# DCM_module_board.net
KiCad netlist of a schematic drawn in EAGLE
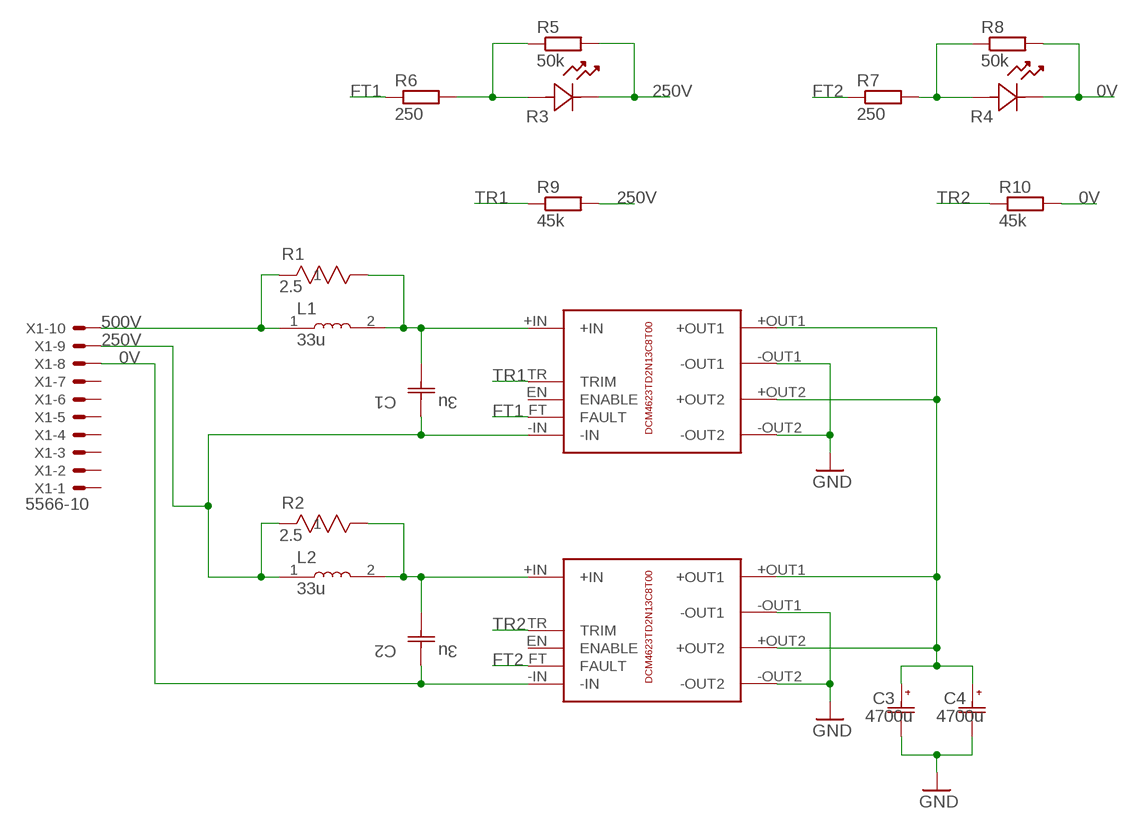
[diagram p0: schematic, sheet 1]

(export (version "E")
  (design (tool "Eeschema 10.0.6"))
  (components
    (comp (ref "C1")
      (value "3u")
      (footprint "eagle-import:CAP_B58035U5305M062_TDK")
      (fields
        (field (name "MANUFACTURER_PART_NUMBER") "B58035U5305M062")
        (field (name "COPYRIGHT") "Copyright (C) 2018 Accelerated Designs. All rights reserved")
      )
      (libsource (lib "eagle-import") (part "B58035U5305M062"))
    )
    (comp (ref "C2")
      (value "3u")
      (footprint "eagle-import:CAP_B58035U5305M062_TDK")
      (fields
        (field (name "MANUFACTURER_PART_NUMBER") "B58035U5305M062")
        (field (name "COPYRIGHT") "Copyright (C) 2018 Accelerated Designs. All rights reserved")
      )
      (libsource (lib "eagle-import") (part "B58035U5305M062"))
    )
    (comp (ref "C3")
      (value "4700u")
      (footprint "eagle-import:CAP_UBX_16X25_NCH")
      (fields
        (field (name "MANUFACTURER_PART_NUMBER") "UBY1E472MHL1TN")
        (field (name "COPYRIGHT") "Copyright (C) 2018 Accelerated Designs. All rights reserved")
      )
      (libsource (lib "eagle-import") (part "UBY1E472MHL1TN"))
    )
    (comp (ref "C4")
      (value "4700u")
      (footprint "eagle-import:CAP_UBX_16X25_NCH")
      (fields
        (field (name "MANUFACTURER_PART_NUMBER") "UBY1E472MHL1TN")
        (field (name "COPYRIGHT") "Copyright (C) 2018 Accelerated Designs. All rights reserved")
      )
      (libsource (lib "eagle-import") (part "UBY1E472MHL1TN"))
    )
    (comp (ref "L1")
      (value "33u")
      (footprint "eagle-import:IND_SRP1265A-330M")
      (fields
        (field (name "DIGI-KEY_PART_NUMBER") "SRP1265A-330MCT-ND")
        (field (name "MF") "Bourns")
        (field (name "MP") "SRP1265A-330M")
      )
      (libsource (lib "eagle-import") (part "SRP1265A-330M"))
    )
    (comp (ref "L2")
      (value "33u")
      (footprint "eagle-import:IND_SRP1265A-330M")
      (fields
        (field (name "DIGI-KEY_PART_NUMBER") "SRP1265A-330MCT-ND")
        (field (name "MF") "Bourns")
        (field (name "MP") "SRP1265A-330M")
      )
      (libsource (lib "eagle-import") (part "SRP1265A-330M"))
    )
    (comp (ref "R1")
      (value "2.5")
      (footprint "eagle-import:RES_TEH100_OHM")
      (fields (field (name "MANUFACTURER_PART_NUMBER") "TEH100M2R50FE"))
      (libsource (lib "eagle-import") (part "TEH100M2R50FE"))
    )
    (comp (ref "R2")
      (value "2.5")
      (footprint "eagle-import:RES_TEH100_OHM")
      (fields (field (name "MANUFACTURER_PART_NUMBER") "TEH100M2R50FE"))
      (libsource (lib "eagle-import") (part "TEH100M2R50FE"))
    )
    (comp (ref "R3")
      (value "SLR-56VR3F")
      (footprint "eagle-import:LED_SLR-56_ROM")
      (fields (field (name "COPYRIGHT") "Copyright (C) 2018 Accelerated Designs. All rights reserved"))
      (libsource (lib "eagle-import") (part "SLR-56VR3F"))
    )
    (comp (ref "R4")
      (value "SLR-56VR3F")
      (footprint "eagle-import:LED_SLR-56_ROM")
      (fields (field (name "COPYRIGHT") "Copyright (C) 2018 Accelerated Designs. All rights reserved"))
      (libsource (lib "eagle-import") (part "SLR-56VR3F"))
    )
    (comp (ref "R5")
      (value "50k")
      (footprint "eagle-import:R0805")
      (libsource (lib "eagle-import") (part "R-EU_R0805"))
    )
    (comp (ref "R6")
      (value "250")
      (footprint "eagle-import:R0805")
      (libsource (lib "eagle-import") (part "R-EU_R0805"))
    )
    (comp (ref "R7")
      (value "250")
      (footprint "eagle-import:R0805")
      (libsource (lib "eagle-import") (part "R-EU_R0805"))
    )
    (comp (ref "R8")
      (value "50k")
      (footprint "eagle-import:R0805")
      (libsource (lib "eagle-import") (part "R-EU_R0805"))
    )
    (comp (ref "R9")
      (value "45k")
      (footprint "eagle-import:R0805")
      (libsource (lib "eagle-import") (part "R-EU_R0805"))
    )
    (comp (ref "R10")
      (value "45k")
      (footprint "eagle-import:R0805")
      (libsource (lib "eagle-import") (part "R-EU_R0805"))
    )
    (comp (ref "U$1")
      (value "DCM4623TD2N13C8T00")
      (footprint "eagle-import:DCM4623TD2N13C8T00")
      (libsource (lib "eagle-import") (part "DCM4623TD2N13C8T00"))
    )
    (comp (ref "U$2")
      (value "DCM4623TD2N13C8T00")
      (footprint "eagle-import:DCM4623TD2N13C8T00")
      (libsource (lib "eagle-import") (part "DCM4623TD2N13C8T00"))
    )
    (comp (ref "X1")
      (value "5566-10")
      (footprint "eagle-import:5566-10")
      (fields (field (name "MF") "MOLEX"))
      (libsource (lib "eagle-import") (part "5566-10"))
    )
  )
  (nets
    (net (code "1") (name "/0V") (class "Default")
      (node (ref "C2") (pin "1") (pinfunction "1_1") (pintype "passive"))
      (node (ref "R10") (pin "2") (pinfunction "2_2") (pintype "passive"))
      (node (ref "R4") (pin "1") (pinfunction "1_1") (pintype "passive"))
      (node (ref "R8") (pin "2") (pinfunction "2_2") (pintype "passive"))
      (node (ref "U$2") (pin "-IN") (pinfunction "-IN_-IN") (pintype "bidirectional"))
      (node (ref "X1") (pin "8") (pinfunction "S_8") (pintype "passive"))
    )
    (net (code "2") (name "/250V") (class "Default")
      (node (ref "C1") (pin "1") (pinfunction "1_1") (pintype "passive"))
      (node (ref "L2") (pin "1") (pinfunction "1_1") (pintype "passive"))
      (node (ref "R2") (pin "1") (pinfunction "1_1") (pintype "passive"))
      (node (ref "R3") (pin "1") (pinfunction "1_1") (pintype "passive"))
      (node (ref "R5") (pin "2") (pinfunction "2_2") (pintype "passive"))
      (node (ref "R9") (pin "2") (pinfunction "2_2") (pintype "passive"))
      (node (ref "U$1") (pin "-IN") (pinfunction "-IN_-IN") (pintype "bidirectional"))
      (node (ref "X1") (pin "9") (pinfunction "S_9") (pintype "passive"))
    )
    (net (code "3") (name "/500V") (class "Default")
      (node (ref "L1") (pin "1") (pinfunction "1_1") (pintype "passive"))
      (node (ref "R1") (pin "1") (pinfunction "1_1") (pintype "passive"))
      (node (ref "X1") (pin "10") (pinfunction "S_10") (pintype "passive"))
    )
    (net (code "4") (name "/FT1") (class "Default")
      (node (ref "R6") (pin "1") (pinfunction "1_1") (pintype "passive"))
      (node (ref "U$1") (pin "FT") (pinfunction "FAULT_FT") (pintype "bidirectional"))
    )
    (net (code "5") (name "/FT2") (class "Default")
      (node (ref "R7") (pin "1") (pinfunction "1_1") (pintype "passive"))
      (node (ref "U$2") (pin "FT") (pinfunction "FAULT_FT") (pintype "bidirectional"))
    )
    (net (code "6") (name "/TR1") (class "Default")
      (node (ref "R9") (pin "1") (pinfunction "1_1") (pintype "passive"))
      (node (ref "U$1") (pin "TR") (pinfunction "TRIM_TR") (pintype "bidirectional"))
    )
    (net (code "7") (name "/TR2") (class "Default")
      (node (ref "R10") (pin "1") (pinfunction "1_1") (pintype "passive"))
      (node (ref "U$2") (pin "TR") (pinfunction "TRIM_TR") (pintype "bidirectional"))
    )
    (net (code "8") (name "GND") (class "Default")
      (node (ref "C3") (pin "2") (pinfunction "2_2") (pintype "passive"))
      (node (ref "C4") (pin "2") (pinfunction "2_2") (pintype "passive"))
      (node (ref "U$1") (pin "-OUT1") (pinfunction "-OUT1_-OUT1") (pintype "bidirectional"))
      (node (ref "U$1") (pin "-OUT2") (pinfunction "-OUT2_-OUT2") (pintype "bidirectional"))
      (node (ref "U$2") (pin "-OUT1") (pinfunction "-OUT1_-OUT1") (pintype "bidirectional"))
      (node (ref "U$2") (pin "-OUT2") (pinfunction "-OUT2_-OUT2") (pintype "bidirectional"))
    )
    (net (code "9") (name "Net-(C3-Pad1)") (class "Default")
      (node (ref "C3") (pin "1") (pinfunction "1_1") (pintype "passive"))
      (node (ref "C4") (pin "1") (pinfunction "1_1") (pintype "passive"))
      (node (ref "U$1") (pin "+OUT1") (pinfunction "+OUT1_+OUT1") (pintype "bidirectional"))
      (node (ref "U$1") (pin "+OUT2") (pinfunction "+OUT2_+OUT2") (pintype "bidirectional"))
      (node (ref "U$2") (pin "+OUT1") (pinfunction "+OUT1_+OUT1") (pintype "bidirectional"))
      (node (ref "U$2") (pin "+OUT2") (pinfunction "+OUT2_+OUT2") (pintype "bidirectional"))
    )
    (net (code "10") (name "Net-(R1-2)") (class "Default")
      (node (ref "C1") (pin "2") (pinfunction "2_2") (pintype "passive"))
      (node (ref "L1") (pin "2") (pinfunction "2_2") (pintype "passive"))
      (node (ref "R1") (pin "3") (pinfunction "2_3") (pintype "passive"))
      (node (ref "U$1") (pin "+IN") (pinfunction "+IN_+IN") (pintype "bidirectional"))
    )
    (net (code "11") (name "Net-(R2-2)") (class "Default")
      (node (ref "C2") (pin "2") (pinfunction "2_2") (pintype "passive"))
      (node (ref "L2") (pin "2") (pinfunction "2_2") (pintype "passive"))
      (node (ref "R2") (pin "3") (pinfunction "2_3") (pintype "passive"))
      (node (ref "U$2") (pin "+IN") (pinfunction "+IN_+IN") (pintype "bidirectional"))
    )
    (net (code "12") (name "Net-(R3-Pad2)") (class "Default")
      (node (ref "R3") (pin "2") (pinfunction "2_2") (pintype "passive"))
      (node (ref "R5") (pin "1") (pinfunction "1_1") (pintype "passive"))
      (node (ref "R6") (pin "2") (pinfunction "2_2") (pintype "passive"))
    )
    (net (code "13") (name "Net-(R4-Pad2)") (class "Default")
      (node (ref "R4") (pin "2") (pinfunction "2_2") (pintype "passive"))
      (node (ref "R7") (pin "2") (pinfunction "2_2") (pintype "passive"))
      (node (ref "R8") (pin "1") (pinfunction "1_1") (pintype "passive"))
    )
    (net (code "14") (name "unconnected-(U$1-ENABLE-PadEN)") (class "Default")
      (node (ref "U$1") (pin "EN") (pinfunction "ENABLE_EN") (pintype "bidirectional"))
    )
    (net (code "15") (name "unconnected-(U$2-ENABLE-PadEN)") (class "Default")
      (node (ref "U$2") (pin "EN") (pinfunction "ENABLE_EN") (pintype "bidirectional"))
    )
    (net (code "16") (name "unconnected-(X1A-S-Pad1)") (class "Default")
      (node (ref "X1") (pin "1") (pinfunction "S_1") (pintype "passive"))
    )
    (net (code "17") (name "unconnected-(X1C-S-Pad2)") (class "Default")
      (node (ref "X1") (pin "2") (pinfunction "S_2") (pintype "passive"))
    )
    (net (code "18") (name "unconnected-(X1D-S-Pad3)") (class "Default")
      (node (ref "X1") (pin "3") (pinfunction "S_3") (pintype "passive"))
    )
    (net (code "19") (name "unconnected-(X1E-S-Pad4)") (class "Default")
      (node (ref "X1") (pin "4") (pinfunction "S_4") (pintype "passive"))
    )
    (net (code "20") (name "unconnected-(X1F-S-Pad5)") (class "Default")
      (node (ref "X1") (pin "5") (pinfunction "S_5") (pintype "passive"))
    )
    (net (code "21") (name "unconnected-(X1G-S-Pad6)") (class "Default")
      (node (ref "X1") (pin "6") (pinfunction "S_6") (pintype "passive"))
    )
    (net (code "22") (name "unconnected-(X1H-S-Pad7)") (class "Default")
      (node (ref "X1") (pin "7") (pinfunction "S_7") (pintype "passive"))
    )
  )
)
